# MCU.net
KiCad netlist of a schematic drawn in Altium Designer
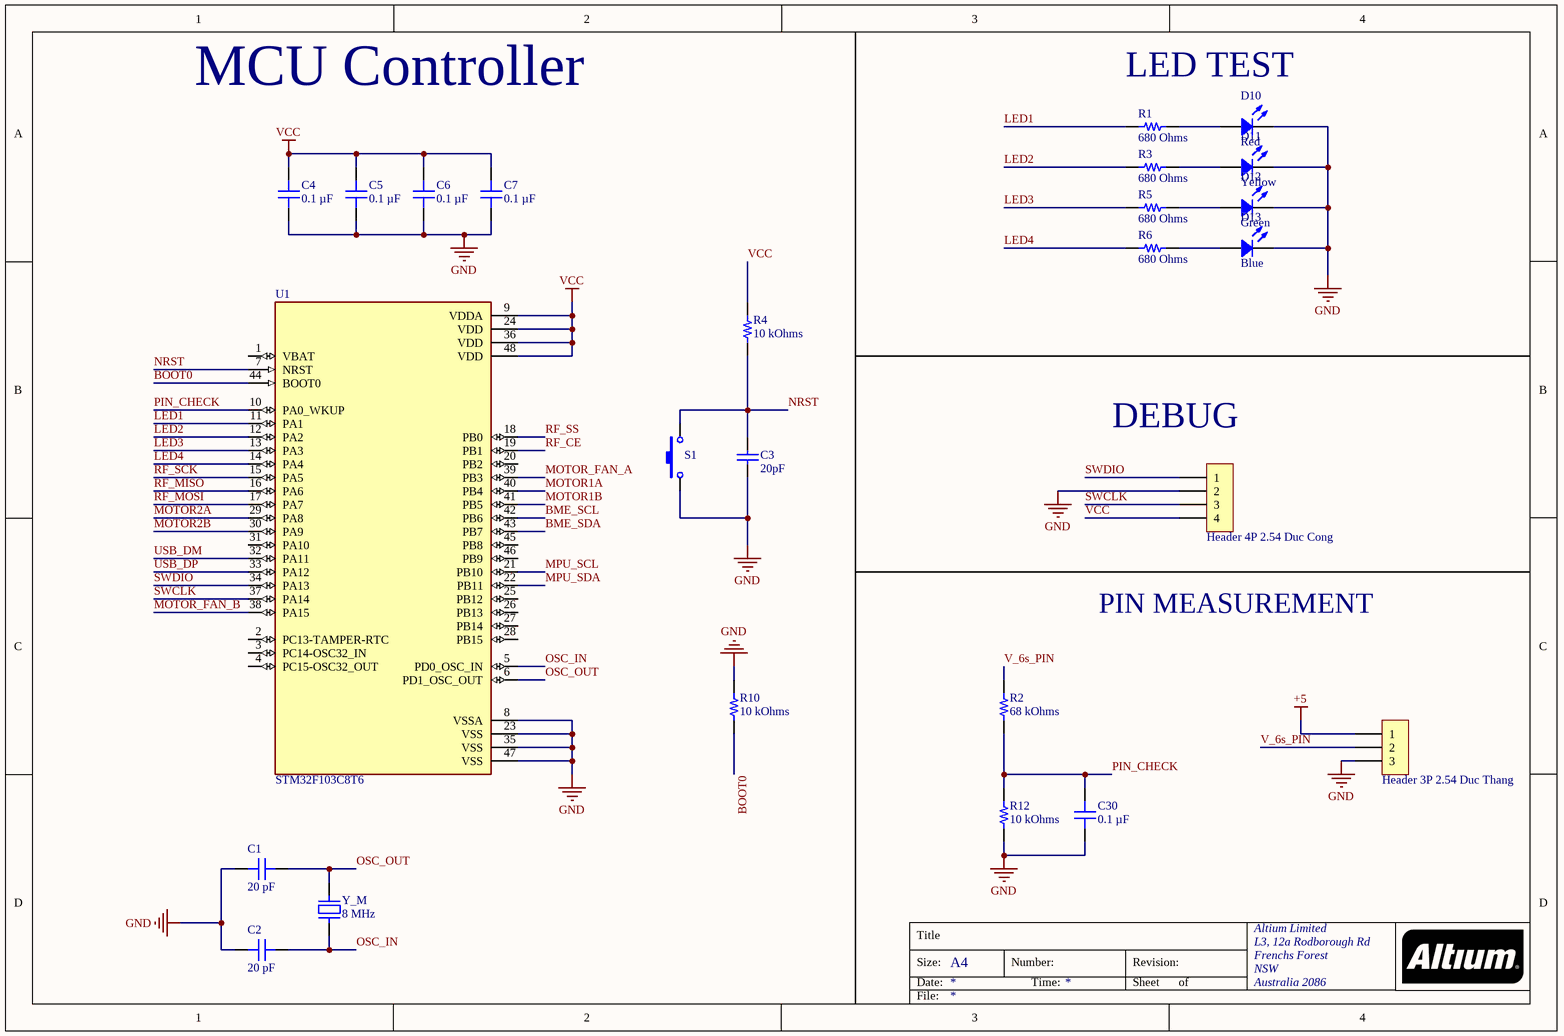
[diagram p0: MCU.SchDoc]

(export (version "E")
  (design (tool "Eeschema 10.0.6"))
  (components
    (comp (ref "C1")
      (value "20 pF")
      (footprint "CAP 0603_1608")
      (description "CAP CER 20PF 10V X8R 0603")
      (fields (field (name "PART NUMBER") "C0603C200K8HAC7867") (field (name "MANUFACTURER") "KEMET"))
      (libsource (lib "Celestial Altium Library - altium_library") (part "Capacitor"))
    )
    (comp (ref "C2")
      (value "20 pF")
      (footprint "CAP 0603_1608")
      (description "CAP CER 20PF 10V X8R 0603")
      (fields (field (name "PART NUMBER") "C0603C200K8HAC7867") (field (name "MANUFACTURER") "KEMET"))
      (libsource (lib "Celestial Altium Library - altium_library") (part "Capacitor"))
    )
    (comp (ref "C3")
      (value "20pF")
      (footprint "tu 0805")
      (description "Dán")
      (libsource (lib "Tu dien") (part "Tu 0805 20pF 50V 10%"))
    )
    (comp (ref "C4")
      (value "0.1 µF")
      (footprint "CAP 0603_1608")
      (description "CAP CER 0.1UF 10V X7R 0603")
      (fields
        (field (name "PART NUMBER") "VJ0603Y104MXQCW1BC")
        (field (name "MANUFACTURER") "Vishay Vitramon")
      )
      (libsource (lib "Celestial Altium Library - altium_library") (part "Capacitor"))
    )
    (comp (ref "C5")
      (value "0.1 µF")
      (footprint "CAP 0603_1608")
      (description "CAP CER 0.1UF 10V X7R 0603")
      (fields
        (field (name "PART NUMBER") "VJ0603Y104MXQCW1BC")
        (field (name "MANUFACTURER") "Vishay Vitramon")
      )
      (libsource (lib "Celestial Altium Library - altium_library") (part "Capacitor"))
    )
    (comp (ref "C6")
      (value "0.1 µF")
      (footprint "CAP 0603_1608")
      (description "CAP CER 0.1UF 10V X7R 0603")
      (fields
        (field (name "PART NUMBER") "VJ0603Y104MXQCW1BC")
        (field (name "MANUFACTURER") "Vishay Vitramon")
      )
      (libsource (lib "Celestial Altium Library - altium_library") (part "Capacitor"))
    )
    (comp (ref "C7")
      (value "0.1 µF")
      (footprint "CAP 0603_1608")
      (description "CAP CER 0.1UF 10V X7R 0603")
      (fields
        (field (name "PART NUMBER") "VJ0603Y104MXQCW1BC")
        (field (name "MANUFACTURER") "Vishay Vitramon")
      )
      (libsource (lib "Celestial Altium Library - altium_library") (part "Capacitor"))
    )
    (comp (ref "C30")
      (value "0.1 µF")
      (footprint "CAP 0603_1608")
      (description "CAP CER 0.1UF 10V X7R 0603")
      (fields
        (field (name "PART NUMBER") "VJ0603Y104KXQCW1BC")
        (field (name "MANUFACTURER") "Vishay Vitramon")
      )
      (libsource (lib "Celestial Altium Library - altium_library") (part "Capacitor"))
    )
    (comp (ref "D10")
      (value "Red")
      (footprint "LED 0603_1608 RED")
      (description "LED RED DIFFUSED 0603 SMD")
      (fields (field (name "PART NUMBER") "5975112402F") (field (name "MANUFACTURER") "Dialight"))
      (libsource (lib "Celestial Altium Library - altium_library") (part "LED"))
    )
    (comp (ref "D11")
      (value "Yellow")
      (footprint "LED 0603_1608 YELLOW")
      (description "LED YELLOW DIFFUSED 1608 SMD")
      (fields (field (name "PART NUMBER") "SML-D15YWT86") (field (name "MANUFACTURER") "Rohm Semiconductor"))
      (libsource (lib "Celestial Altium Library - altium_library") (part "LED"))
    )
    (comp (ref "D12")
      (value "Green")
      (footprint "LED 0603_1608 GREEN")
      (description "LED GREEN DIFFUSED 1608 SMD")
      (fields (field (name "PART NUMBER") "SML-D13M8WT86") (field (name "MANUFACTURER") "Rohm Semiconductor"))
      (libsource (lib "Celestial Altium Library - altium_library") (part "LED"))
    )
    (comp (ref "D13")
      (value "Blue")
      (footprint "LED 0603_1608 BLUE")
      (description "LED BLUE DIFFUSED 0603 SMD")
      (fields
        (field (name "PART NUMBER") "LB Q39G-L2OO-35-1")
        (field (name "MANUFACTURER") "OSRAM Opto Semiconductors Inc.")
      )
      (libsource (lib "Celestial Altium Library - altium_library") (part "LED"))
    )
    (comp (ref "H5")
      (value "Header 4P 2.54 Duc Cong")
      (footprint "Header 4P DC 2.54")
      (description "Cắm")
      (libsource (lib "Header") (part "Header 4P 2.54 Duc Cong"))
    )
    (comp (ref "H8")
      (value "Header 3P 2.54 Duc Thang")
      (footprint "XH2.54M-3")
      (description "Cắm")
      (libsource (lib "Header") (part "Header 3P 2.54 Duc Thang"))
    )
    (comp (ref "R1")
      (value "680 Ohms")
      (footprint "RES 0603_1608")
      (description "RES 680 OHM 1% 1/10W 0603")
      (fields
        (field (name "PART NUMBER") "CRGCQ0603F680R")
        (field (name "MANUFACTURER") "TE Connectivity Passive Product")
      )
      (libsource (lib "Celestial Altium Library - altium_library") (part "Resistor"))
    )
    (comp (ref "R2")
      (value "68 kOhms")
      (footprint "RES 0805_2012")
      (description "RES SMD 68K OHM 0.5% 1/10W 0805")
      (fields (field (name "PART NUMBER") "RR1220P-683-D") (field (name "MANUFACTURER") "Susumu"))
      (libsource (lib "Celestial Altium Library - altium_library") (part "Resistor"))
    )
    (comp (ref "R3")
      (value "680 Ohms")
      (footprint "RES 0603_1608")
      (description "RES 680 OHM 1% 1/10W 0603")
      (fields
        (field (name "PART NUMBER") "CRGCQ0603F680R")
        (field (name "MANUFACTURER") "TE Connectivity Passive Product")
      )
      (libsource (lib "Celestial Altium Library - altium_library") (part "Resistor"))
    )
    (comp (ref "R4")
      (value "10 kOhms")
      (footprint "RES 0603_1608")
      (description "RES SMD 10K OHM 1% 1/10W 0603")
      (fields (field (name "PART NUMBER") "CRCW060310K0FHEAP") (field (name "MANUFACTURER") "Vishay Dale"))
      (libsource (lib "Celestial Altium Library - altium_library") (part "Resistor"))
    )
    (comp (ref "R5")
      (value "680 Ohms")
      (footprint "RES 0603_1608")
      (description "RES 680 OHM 1% 1/10W 0603")
      (fields
        (field (name "PART NUMBER") "CRGCQ0603F680R")
        (field (name "MANUFACTURER") "TE Connectivity Passive Product")
      )
      (libsource (lib "Celestial Altium Library - altium_library") (part "Resistor"))
    )
    (comp (ref "R6")
      (value "680 Ohms")
      (footprint "RES 0603_1608")
      (description "RES 680 OHM 1% 1/10W 0603")
      (fields
        (field (name "PART NUMBER") "CRGCQ0603F680R")
        (field (name "MANUFACTURER") "TE Connectivity Passive Product")
      )
      (libsource (lib "Celestial Altium Library - altium_library") (part "Resistor"))
    )
    (comp (ref "R10")
      (value "10 kOhms")
      (footprint "RES 0603_1608")
      (description "RES SMD 10K OHM 1% 1/10W 0603")
      (fields (field (name "PART NUMBER") "CRCW060310K0FHEAP") (field (name "MANUFACTURER") "Vishay Dale"))
      (libsource (lib "Celestial Altium Library - altium_library") (part "Resistor"))
    )
    (comp (ref "R12")
      (value "10 kOhms")
      (footprint "RES 0805_2012")
      (description "RES 10K OHM 0.1% 1/10W 0805")
      (fields
        (field (name "PART NUMBER") "RNCS0805BKE10K0")
        (field (name "MANUFACTURER") "Stackpole Electronics Inc")
      )
      (libsource (lib "Celestial Altium Library - altium_library") (part "Resistor"))
    )
    (comp (ref "S1")
      (value "SW-SMD")
      (footprint "SW-SMD")
      (description "Switch")
      (fields (field (name "PUBLISHER") "Altium Limited"))
      (libsource (lib "NBBLib 14-03-2012") (part "SW-SMD"))
    )
    (comp (ref "U1")
      (value "STM32F103C8T6")
      (footprint "QFP50P900X900X160-48N")
      (description "ARMÂ® CortexÂ®-M3 STM32F1 Microcontroller IC 32-Bit 72MHz 64KB (64K x 8) FLASH 48-LQFP (7x7)")
      (fields (field (name "MF") "STMicroelectronics"))
      (libsource (lib "STM32F103C8T6") (part "STM32F103C8T6"))
    )
    (comp (ref "Y_M")
      (value "8 MHz")
      (footprint "NDK NX5032GA")
      (description "CRYSTAL 8.0000MHZ 18PF SMD")
      (fields
        (field (name "PART NUMBER") "NX5032GA-8MHZ-EXS00A-CG07039")
        (field (name "MANUFACTURER") "NDK America, Inc.")
      )
      (libsource (lib "Celestial Altium Library - altium_library") (part "NDK Crystal NX5032GA"))
    )
  )
  (nets
    (net (code "1") (name "+5") (class "Default")
      (node (ref "H8") (pin "1") (pinfunction "1_1") (pintype "passive"))
    )
    (net (code "2") (name "/BME_SCL") (class "Default")
      (node (ref "U1") (pin "42") (pinfunction "PB6_42") (pintype "bidirectional"))
    )
    (net (code "3") (name "/BME_SDA") (class "Default")
      (node (ref "U1") (pin "43") (pinfunction "PB7_43") (pintype "bidirectional"))
    )
    (net (code "4") (name "/BOOT0") (class "Default")
      (node (ref "R10") (pin "2") (pinfunction "2_2") (pintype "passive"))
      (node (ref "U1") (pin "44") (pinfunction "BOOT0_44") (pintype "input"))
    )
    (net (code "5") (name "/LED1") (class "Default")
      (node (ref "R1") (pin "1") (pinfunction "1_1") (pintype "passive"))
      (node (ref "U1") (pin "11") (pinfunction "PA1_11") (pintype "bidirectional"))
    )
    (net (code "6") (name "/LED2") (class "Default")
      (node (ref "R3") (pin "1") (pinfunction "1_1") (pintype "passive"))
      (node (ref "U1") (pin "12") (pinfunction "PA2_12") (pintype "bidirectional"))
    )
    (net (code "7") (name "/LED3") (class "Default")
      (node (ref "R5") (pin "1") (pinfunction "1_1") (pintype "passive"))
      (node (ref "U1") (pin "13") (pinfunction "PA3_13") (pintype "bidirectional"))
    )
    (net (code "8") (name "/LED4") (class "Default")
      (node (ref "R6") (pin "1") (pinfunction "1_1") (pintype "passive"))
      (node (ref "U1") (pin "14") (pinfunction "PA4_14") (pintype "bidirectional"))
    )
    (net (code "9") (name "/MOTOR1A") (class "Default")
      (node (ref "U1") (pin "40") (pinfunction "PB4_40") (pintype "bidirectional"))
    )
    (net (code "10") (name "/MOTOR1B") (class "Default")
      (node (ref "U1") (pin "41") (pinfunction "PB5_41") (pintype "bidirectional"))
    )
    (net (code "11") (name "/MOTOR2A") (class "Default")
      (node (ref "U1") (pin "29") (pinfunction "PA8_29") (pintype "bidirectional"))
    )
    (net (code "12") (name "/MOTOR2B") (class "Default")
      (node (ref "U1") (pin "30") (pinfunction "PA9_30") (pintype "bidirectional"))
    )
    (net (code "13") (name "/MOTOR_FAN_A") (class "Default")
      (node (ref "U1") (pin "39") (pinfunction "PB3_39") (pintype "bidirectional"))
    )
    (net (code "14") (name "/MOTOR_FAN_B") (class "Default")
      (node (ref "U1") (pin "38") (pinfunction "PA15_38") (pintype "bidirectional"))
    )
    (net (code "15") (name "/MPU_SCL") (class "Default")
      (node (ref "U1") (pin "21") (pinfunction "PB10_21") (pintype "bidirectional"))
    )
    (net (code "16") (name "/MPU_SDA") (class "Default")
      (node (ref "U1") (pin "22") (pinfunction "PB11_22") (pintype "bidirectional"))
    )
    (net (code "17") (name "/NRST") (class "Default")
      (node (ref "C3") (pin "1") (pinfunction "1_1") (pintype "passive"))
      (node (ref "R4") (pin "1") (pinfunction "1_1") (pintype "passive"))
      (node (ref "S1") (pin "2") (pinfunction "2_2") (pintype "passive"))
      (node (ref "U1") (pin "7") (pinfunction "NRST_7") (pintype "input"))
    )
    (net (code "18") (name "/OSC_IN") (class "Default")
      (node (ref "C2") (pin "2") (pinfunction "2_2") (pintype "passive"))
      (node (ref "U1") (pin "5") (pinfunction "PD0_OSC_IN_5") (pintype "bidirectional"))
      (node (ref "Y_M") (pin "2") (pinfunction "2_2") (pintype "passive"))
    )
    (net (code "19") (name "/OSC_OUT") (class "Default")
      (node (ref "C1") (pin "2") (pinfunction "2_2") (pintype "passive"))
      (node (ref "U1") (pin "6") (pinfunction "PD1_OSC_OUT_6") (pintype "bidirectional"))
      (node (ref "Y_M") (pin "1") (pinfunction "1_1") (pintype "passive"))
    )
    (net (code "20") (name "/PIN_CHECK") (class "Default")
      (node (ref "C30") (pin "2") (pinfunction "2_2") (pintype "passive"))
      (node (ref "R12") (pin "2") (pinfunction "2_2") (pintype "passive"))
      (node (ref "R2") (pin "1") (pinfunction "1_1") (pintype "passive"))
      (node (ref "U1") (pin "10") (pinfunction "PA0_WKUP_10") (pintype "bidirectional"))
    )
    (net (code "21") (name "/RF_CE") (class "Default")
      (node (ref "U1") (pin "19") (pinfunction "PB1_19") (pintype "bidirectional"))
    )
    (net (code "22") (name "/RF_MISO") (class "Default")
      (node (ref "U1") (pin "16") (pinfunction "PA6_16") (pintype "bidirectional"))
    )
    (net (code "23") (name "/RF_MOSI") (class "Default")
      (node (ref "U1") (pin "17") (pinfunction "PA7_17") (pintype "bidirectional"))
    )
    (net (code "24") (name "/RF_SCK") (class "Default")
      (node (ref "U1") (pin "15") (pinfunction "PA5_15") (pintype "bidirectional"))
    )
    (net (code "25") (name "/RF_SS") (class "Default")
      (node (ref "U1") (pin "18") (pinfunction "PB0_18") (pintype "bidirectional"))
    )
    (net (code "26") (name "/SWCLK") (class "Default")
      (node (ref "H5") (pin "3") (pinfunction "3_3") (pintype "passive"))
      (node (ref "U1") (pin "37") (pinfunction "PA14_37") (pintype "bidirectional"))
    )
    (net (code "27") (name "/SWDIO") (class "Default")
      (node (ref "H5") (pin "1") (pinfunction "1_1") (pintype "passive"))
      (node (ref "U1") (pin "34") (pinfunction "PA13_34") (pintype "bidirectional"))
    )
    (net (code "28") (name "/USB_DM") (class "Default")
      (node (ref "U1") (pin "32") (pinfunction "PA11_32") (pintype "bidirectional"))
    )
    (net (code "29") (name "/USB_DP") (class "Default")
      (node (ref "U1") (pin "33") (pinfunction "PA12_33") (pintype "bidirectional"))
    )
    (net (code "30") (name "/V_6s_PIN") (class "Default")
      (node (ref "H8") (pin "2") (pinfunction "2_2") (pintype "passive"))
      (node (ref "R2") (pin "2") (pinfunction "2_2") (pintype "passive"))
    )
    (net (code "31") (name "GND") (class "Default")
      (node (ref "C1") (pin "1") (pinfunction "1_1") (pintype "passive"))
      (node (ref "C2") (pin "1") (pinfunction "1_1") (pintype "passive"))
      (node (ref "C3") (pin "2") (pinfunction "2_2") (pintype "passive"))
      (node (ref "C30") (pin "1") (pinfunction "1_1") (pintype "passive"))
      (node (ref "C4") (pin "1") (pinfunction "1_1") (pintype "passive"))
      (node (ref "C5") (pin "1") (pinfunction "1_1") (pintype "passive"))
      (node (ref "C6") (pin "1") (pinfunction "1_1") (pintype "passive"))
      (node (ref "C7") (pin "1") (pinfunction "1_1") (pintype "passive"))
      (node (ref "D10") (pin "2") (pinfunction "2_2") (pintype "passive"))
      (node (ref "D11") (pin "2") (pinfunction "2_2") (pintype "passive"))
      (node (ref "D12") (pin "2") (pinfunction "2_2") (pintype "passive"))
      (node (ref "D13") (pin "2") (pinfunction "2_2") (pintype "passive"))
      (node (ref "H5") (pin "2") (pinfunction "2_2") (pintype "passive"))
      (node (ref "H8") (pin "3") (pinfunction "3_3") (pintype "passive"))
      (node (ref "R10") (pin "1") (pinfunction "1_1") (pintype "passive"))
      (node (ref "R12") (pin "1") (pinfunction "1_1") (pintype "passive"))
      (node (ref "S1") (pin "1") (pinfunction "1_1") (pintype "passive"))
      (node (ref "U1") (pin "23") (pinfunction "VSS_23") (pintype "power_in"))
      (node (ref "U1") (pin "35") (pinfunction "VSS_35") (pintype "power_in"))
      (node (ref "U1") (pin "47") (pinfunction "VSS_47") (pintype "power_in"))
      (node (ref "U1") (pin "8") (pinfunction "VSSA_8") (pintype "power_in"))
    )
    (net (code "32") (name "Net-(D10-Pad1)") (class "Default")
      (node (ref "D10") (pin "1") (pinfunction "1_1") (pintype "passive"))
      (node (ref "R1") (pin "2") (pinfunction "2_2") (pintype "passive"))
    )
    (net (code "33") (name "Net-(D11-Pad1)") (class "Default")
      (node (ref "D11") (pin "1") (pinfunction "1_1") (pintype "passive"))
      (node (ref "R3") (pin "2") (pinfunction "2_2") (pintype "passive"))
    )
    (net (code "34") (name "Net-(D12-Pad1)") (class "Default")
      (node (ref "D12") (pin "1") (pinfunction "1_1") (pintype "passive"))
      (node (ref "R5") (pin "2") (pinfunction "2_2") (pintype "passive"))
    )
    (net (code "35") (name "Net-(D13-Pad1)") (class "Default")
      (node (ref "D13") (pin "1") (pinfunction "1_1") (pintype "passive"))
      (node (ref "R6") (pin "2") (pinfunction "2_2") (pintype "passive"))
    )
    (net (code "36") (name "VCC") (class "Default")
      (node (ref "C4") (pin "2") (pinfunction "2_2") (pintype "passive"))
      (node (ref "C5") (pin "2") (pinfunction "2_2") (pintype "passive"))
      (node (ref "C6") (pin "2") (pinfunction "2_2") (pintype "passive"))
      (node (ref "C7") (pin "2") (pinfunction "2_2") (pintype "passive"))
      (node (ref "H5") (pin "4") (pinfunction "4_4") (pintype "passive"))
      (node (ref "R4") (pin "2") (pinfunction "2_2") (pintype "passive"))
      (node (ref "U1") (pin "24") (pinfunction "VDD_24") (pintype "power_in"))
      (node (ref "U1") (pin "36") (pinfunction "VDD_36") (pintype "power_in"))
      (node (ref "U1") (pin "48") (pinfunction "VDD_48") (pintype "power_in"))
      (node (ref "U1") (pin "9") (pinfunction "VDDA_9") (pintype "power_in"))
    )
    (net (code "37") (name "unconnected-(U1-PA10-Pad31)") (class "Default")
      (node (ref "U1") (pin "31") (pinfunction "PA10_31") (pintype "bidirectional"))
    )
    (net (code "38") (name "unconnected-(U1-PB2-Pad20)") (class "Default")
      (node (ref "U1") (pin "20") (pinfunction "PB2_20") (pintype "bidirectional"))
    )
    (net (code "39") (name "unconnected-(U1-PB8-Pad45)") (class "Default")
      (node (ref "U1") (pin "45") (pinfunction "PB8_45") (pintype "bidirectional"))
    )
    (net (code "40") (name "unconnected-(U1-PB9-Pad46)") (class "Default")
      (node (ref "U1") (pin "46") (pinfunction "PB9_46") (pintype "bidirectional"))
    )
    (net (code "41") (name "unconnected-(U1-PB12-Pad25)") (class "Default")
      (node (ref "U1") (pin "25") (pinfunction "PB12_25") (pintype "bidirectional"))
    )
    (net (code "42") (name "unconnected-(U1-PB13-Pad26)") (class "Default")
      (node (ref "U1") (pin "26") (pinfunction "PB13_26") (pintype "bidirectional"))
    )
    (net (code "43") (name "unconnected-(U1-PB14-Pad27)") (class "Default")
      (node (ref "U1") (pin "27") (pinfunction "PB14_27") (pintype "bidirectional"))
    )
    (net (code "44") (name "unconnected-(U1-PB15-Pad28)") (class "Default")
      (node (ref "U1") (pin "28") (pinfunction "PB15_28") (pintype "bidirectional"))
    )
    (net (code "45") (name "unconnected-(U1-PC13-TAMPER-RTC-Pad2)") (class "Default")
      (node (ref "U1") (pin "2") (pinfunction "PC13-TAMPER-RTC_2") (pintype "bidirectional"))
    )
    (net (code "46") (name "unconnected-(U1-PC14-OSC32_IN-Pad3)") (class "Default")
      (node (ref "U1") (pin "3") (pinfunction "PC14-OSC32_IN_3") (pintype "bidirectional"))
    )
    (net (code "47") (name "unconnected-(U1-PC15-OSC32_OUT-Pad4)") (class "Default")
      (node (ref "U1") (pin "4") (pinfunction "PC15-OSC32_OUT_4") (pintype "bidirectional"))
    )
    (net (code "48") (name "unconnected-(U1-VBAT-Pad1)") (class "Default")
      (node (ref "U1") (pin "1") (pinfunction "VBAT_1") (pintype "bidirectional"))
    )
  )
)
